# memory-slice.net
KiCad netlist of a schematic drawn in EAGLE
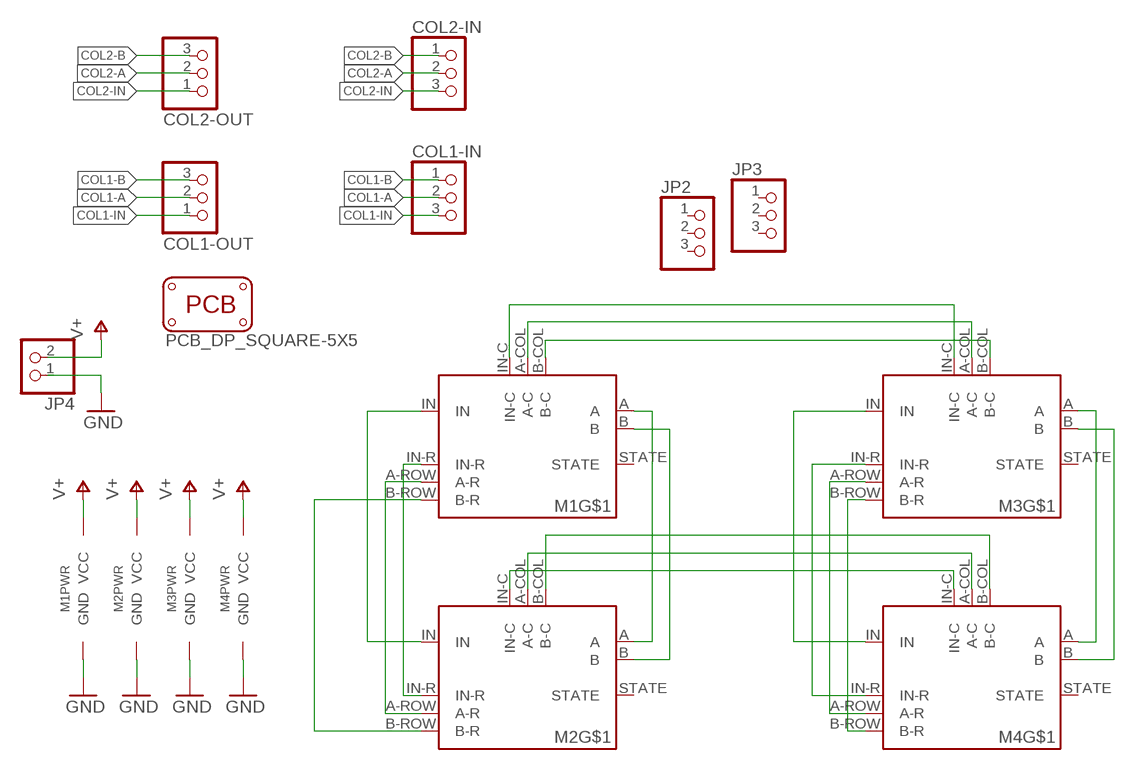
[diagram p0: schematic, sheet 1]

(export (version "E")
  (design (tool "Eeschema 10.0.6"))
  (components
    (comp (ref "COL1-IN")
      (value "PINHD-1X3/90")
      (footprint "eagle-import:1X03_90")
      (libsource (lib "eagle-import") (part "PINHD-1X3/90"))
    )
    (comp (ref "COL1-OUT")
      (value "PINHD-1X3/90")
      (footprint "eagle-import:1X03_90")
      (libsource (lib "eagle-import") (part "PINHD-1X3/90"))
    )
    (comp (ref "COL2-IN")
      (value "PINHD-1X3/90")
      (footprint "eagle-import:1X03_90")
      (libsource (lib "eagle-import") (part "PINHD-1X3/90"))
    )
    (comp (ref "COL2-OUT")
      (value "PINHD-1X3/90")
      (footprint "eagle-import:1X03_90")
      (libsource (lib "eagle-import") (part "PINHD-1X3/90"))
    )
    (comp (ref "JP2")
      (value "PINHD-1X3/90")
      (footprint "eagle-import:1X03_90")
      (libsource (lib "eagle-import") (part "PINHD-1X3/90"))
    )
    (comp (ref "JP3")
      (value "PINHD-1X3/90")
      (footprint "eagle-import:1X03_90")
      (libsource (lib "eagle-import") (part "PINHD-1X3/90"))
    )
    (comp (ref "JP4")
      (value "PINHD-1X2")
      (footprint "eagle-import:1X02")
      (libsource (lib "eagle-import") (part "PINHD-1X2"))
    )
    (comp (ref "M1")
      (value "MEMORY-1BIT-CELL")
      (footprint "eagle-import:MEMORY-1BIT-CELL")
      (libsource (lib "eagle-import") (part "MEMORY-1BIT-CELL"))
    )
    (comp (ref "M2")
      (value "MEMORY-1BIT-CELL")
      (footprint "eagle-import:MEMORY-1BIT-CELL")
      (libsource (lib "eagle-import") (part "MEMORY-1BIT-CELL"))
    )
    (comp (ref "M3")
      (value "MEMORY-1BIT-CELL")
      (footprint "eagle-import:MEMORY-1BIT-CELL")
      (libsource (lib "eagle-import") (part "MEMORY-1BIT-CELL"))
    )
    (comp (ref "M4")
      (value "MEMORY-1BIT-CELL")
      (footprint "eagle-import:MEMORY-1BIT-CELL")
      (libsource (lib "eagle-import") (part "MEMORY-1BIT-CELL"))
    )
    (comp (ref "PCB1")
      (value "PCB_DP_SQUARE-5X5")
      (footprint "eagle-import:DP5050_V1")
      (libsource (lib "eagle-import") (part "PCB_DP_SQUARE-5X5"))
    )
  )
  (nets
    (net (code "1") (name "COL1-A") (class "Default")
      (node (ref "COL1-IN") (pin "2") (pinfunction "2_2") (pintype "passive"))
      (node (ref "COL1-OUT") (pin "2") (pinfunction "2_2") (pintype "passive"))
      (node (ref "M1") (pin "A-COL") (pinfunction "A-C_A-COL") (pintype "input"))
      (node (ref "M3") (pin "A-COL") (pinfunction "A-C_A-COL") (pintype "input"))
    )
    (net (code "2") (name "COL1-B") (class "Default")
      (node (ref "COL1-IN") (pin "1") (pinfunction "1_1") (pintype "passive"))
      (node (ref "COL1-OUT") (pin "3") (pinfunction "3_3") (pintype "passive"))
      (node (ref "M1") (pin "B-COL") (pinfunction "B-C_B-COL") (pintype "input"))
      (node (ref "M3") (pin "B-COL") (pinfunction "B-C_B-COL") (pintype "input"))
    )
    (net (code "3") (name "COL1-IN") (class "Default")
      (node (ref "COL1-IN") (pin "3") (pinfunction "3_3") (pintype "passive"))
      (node (ref "COL1-OUT") (pin "1") (pinfunction "1_1") (pintype "passive"))
      (node (ref "M1") (pin "IN-C") (pinfunction "IN-C_IN-C") (pintype "input"))
      (node (ref "M3") (pin "IN-C") (pinfunction "IN-C_IN-C") (pintype "input"))
    )
    (net (code "4") (name "COL2-A") (class "Default")
      (node (ref "COL2-IN") (pin "2") (pinfunction "2_2") (pintype "passive"))
      (node (ref "COL2-OUT") (pin "2") (pinfunction "2_2") (pintype "passive"))
      (node (ref "M2") (pin "A-COL") (pinfunction "A-C_A-COL") (pintype "input"))
      (node (ref "M4") (pin "A-COL") (pinfunction "A-C_A-COL") (pintype "input"))
    )
    (net (code "5") (name "COL2-B") (class "Default")
      (node (ref "COL2-IN") (pin "1") (pinfunction "1_1") (pintype "passive"))
      (node (ref "COL2-OUT") (pin "3") (pinfunction "3_3") (pintype "passive"))
      (node (ref "M2") (pin "B-COL") (pinfunction "B-C_B-COL") (pintype "input"))
      (node (ref "M4") (pin "B-COL") (pinfunction "B-C_B-COL") (pintype "input"))
    )
    (net (code "6") (name "COL2-IN") (class "Default")
      (node (ref "COL2-IN") (pin "3") (pinfunction "3_3") (pintype "passive"))
      (node (ref "COL2-OUT") (pin "1") (pinfunction "1_1") (pintype "passive"))
      (node (ref "M2") (pin "IN-C") (pinfunction "IN-C_IN-C") (pintype "input"))
      (node (ref "M4") (pin "IN-C") (pinfunction "IN-C_IN-C") (pintype "input"))
    )
    (net (code "7") (name "GND") (class "Default")
      (node (ref "JP4") (pin "1") (pinfunction "1_1") (pintype "passive"))
      (node (ref "M1") (pin "GND") (pinfunction "GND_GND") (pintype "bidirectional"))
      (node (ref "M2") (pin "GND") (pinfunction "GND_GND") (pintype "bidirectional"))
      (node (ref "M3") (pin "GND") (pinfunction "GND_GND") (pintype "bidirectional"))
      (node (ref "M4") (pin "GND") (pinfunction "GND_GND") (pintype "bidirectional"))
    )
    (net (code "8") (name "Net-(M1-PadA)") (class "Default")
      (node (ref "M1") (pin "A") (pinfunction "A_A") (pintype "output"))
      (node (ref "M2") (pin "A") (pinfunction "A_A") (pintype "output"))
    )
    (net (code "9") (name "Net-(M1-PadB)") (class "Default")
      (node (ref "M1") (pin "B") (pinfunction "B_B") (pintype "output"))
      (node (ref "M2") (pin "B") (pinfunction "B_B") (pintype "output"))
    )
    (net (code "10") (name "Net-(M1-PadIN)") (class "Default")
      (node (ref "M1") (pin "IN") (pinfunction "IN_IN") (pintype "input"))
      (node (ref "M2") (pin "IN") (pinfunction "IN_IN") (pintype "input"))
    )
    (net (code "11") (name "Net-(M1-PadIN-R)") (class "Default")
      (node (ref "M1") (pin "IN-R") (pinfunction "IN-R_IN-R") (pintype "input"))
      (node (ref "M2") (pin "IN-R") (pinfunction "IN-R_IN-R") (pintype "input"))
    )
    (net (code "12") (name "Net-(M1A-A-R)") (class "Default")
      (node (ref "M1") (pin "A-ROW") (pinfunction "A-R_A-ROW") (pintype "input"))
      (node (ref "M2") (pin "A-ROW") (pinfunction "A-R_A-ROW") (pintype "input"))
    )
    (net (code "13") (name "Net-(M1A-B-R)") (class "Default")
      (node (ref "M1") (pin "B-ROW") (pinfunction "B-R_B-ROW") (pintype "input"))
      (node (ref "M2") (pin "B-ROW") (pinfunction "B-R_B-ROW") (pintype "input"))
    )
    (net (code "14") (name "Net-(M3-PadA)") (class "Default")
      (node (ref "M3") (pin "A") (pinfunction "A_A") (pintype "output"))
      (node (ref "M4") (pin "A") (pinfunction "A_A") (pintype "output"))
    )
    (net (code "15") (name "Net-(M3-PadB)") (class "Default")
      (node (ref "M3") (pin "B") (pinfunction "B_B") (pintype "output"))
      (node (ref "M4") (pin "B") (pinfunction "B_B") (pintype "output"))
    )
    (net (code "16") (name "Net-(M3-PadIN)") (class "Default")
      (node (ref "M3") (pin "IN") (pinfunction "IN_IN") (pintype "input"))
      (node (ref "M4") (pin "IN") (pinfunction "IN_IN") (pintype "input"))
    )
    (net (code "17") (name "Net-(M3-PadIN-R)") (class "Default")
      (node (ref "M3") (pin "IN-R") (pinfunction "IN-R_IN-R") (pintype "input"))
      (node (ref "M4") (pin "IN-R") (pinfunction "IN-R_IN-R") (pintype "input"))
    )
    (net (code "18") (name "Net-(M3A-A-R)") (class "Default")
      (node (ref "M3") (pin "A-ROW") (pinfunction "A-R_A-ROW") (pintype "input"))
      (node (ref "M4") (pin "A-ROW") (pinfunction "A-R_A-ROW") (pintype "input"))
    )
    (net (code "19") (name "Net-(M3A-B-R)") (class "Default")
      (node (ref "M3") (pin "B-ROW") (pinfunction "B-R_B-ROW") (pintype "input"))
      (node (ref "M4") (pin "B-ROW") (pinfunction "B-R_B-ROW") (pintype "input"))
    )
    (net (code "20") (name "V+") (class "Default")
      (node (ref "JP4") (pin "2") (pinfunction "2_2") (pintype "passive"))
      (node (ref "M1") (pin "VCC") (pinfunction "VCC_VCC") (pintype "bidirectional"))
      (node (ref "M2") (pin "VCC") (pinfunction "VCC_VCC") (pintype "bidirectional"))
      (node (ref "M3") (pin "VCC") (pinfunction "VCC_VCC") (pintype "bidirectional"))
      (node (ref "M4") (pin "VCC") (pinfunction "VCC_VCC") (pintype "bidirectional"))
    )
    (net (code "21") (name "unconnected-(JP2-Pad1)") (class "Default")
      (node (ref "JP2") (pin "1") (pinfunction "1_1") (pintype "passive"))
    )
    (net (code "22") (name "unconnected-(JP2-Pad2)") (class "Default")
      (node (ref "JP2") (pin "2") (pinfunction "2_2") (pintype "passive"))
    )
    (net (code "23") (name "unconnected-(JP2-Pad3)") (class "Default")
      (node (ref "JP2") (pin "3") (pinfunction "3_3") (pintype "passive"))
    )
    (net (code "24") (name "unconnected-(JP3-Pad1)") (class "Default")
      (node (ref "JP3") (pin "1") (pinfunction "1_1") (pintype "passive"))
    )
    (net (code "25") (name "unconnected-(JP3-Pad2)") (class "Default")
      (node (ref "JP3") (pin "2") (pinfunction "2_2") (pintype "passive"))
    )
    (net (code "26") (name "unconnected-(JP3-Pad3)") (class "Default")
      (node (ref "JP3") (pin "3") (pinfunction "3_3") (pintype "passive"))
    )
    (net (code "27") (name "unconnected-(M1-PadSTATE)") (class "Default")
      (node (ref "M1") (pin "STATE") (pinfunction "STATE_STATE") (pintype "output"))
    )
    (net (code "28") (name "unconnected-(M2-PadSTATE)") (class "Default")
      (node (ref "M2") (pin "STATE") (pinfunction "STATE_STATE") (pintype "output"))
    )
    (net (code "29") (name "unconnected-(M3-PadSTATE)") (class "Default")
      (node (ref "M3") (pin "STATE") (pinfunction "STATE_STATE") (pintype "output"))
    )
    (net (code "30") (name "unconnected-(M4-PadSTATE)") (class "Default")
      (node (ref "M4") (pin "STATE") (pinfunction "STATE_STATE") (pintype "output"))
    )
  )
)
